# Dial.net
KiCad netlist of a schematic drawn in Altium Designer
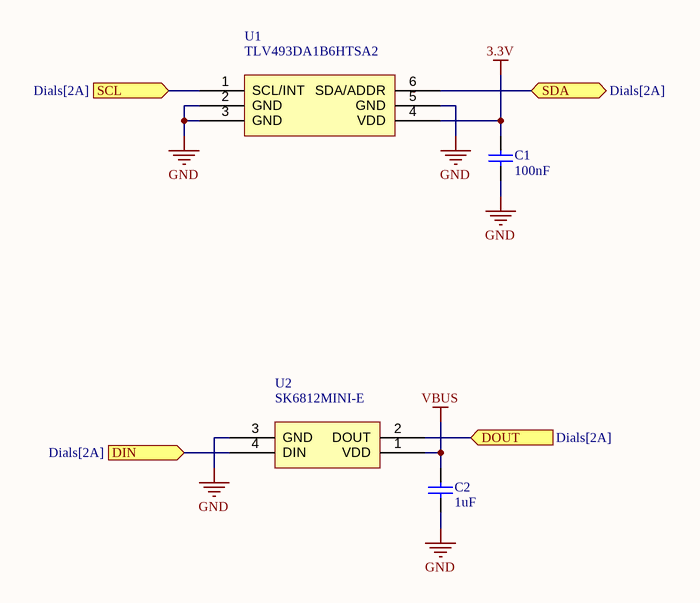
[diagram p0: Dial.SchDoc]

(export (version "E")
  (design (tool "Eeschema 10.0.6"))
  (components
    (comp (ref "C1") (value "100nF") (footprint "Capacitor 0603") (libsource (lib "x-io") (part "Capacitor")))
    (comp (ref "C2") (value "1uF") (footprint "Capacitor 0603") (libsource (lib "x-io") (part "Capacitor")))
    (comp (ref "U1")
      (value "TLV493DA1B6HTSA2")
      (footprint "SOT-23-6")
      (libsource (lib "x-io") (part "TLV493DA1B6HTSA2"))
    )
    (comp (ref "U2")
      (value "SK6812MINI-E")
      (footprint "SK6812MINI-E")
      (libsource (lib "x-io") (part "SK6812MINI-E"))
    )
  )
  (nets
    (net (code "1") (name "/DIN") (class "Default")
      (node (ref "U2") (pin "4") (pinfunction "DIN_4") (pintype "passive"))
    )
    (net (code "2") (name "/DOUT") (class "Default")
      (node (ref "U2") (pin "2") (pinfunction "DOUT_2") (pintype "passive"))
    )
    (net (code "3") (name "/SCL") (class "Default")
      (node (ref "U1") (pin "1") (pinfunction "SCL/INT_1") (pintype "passive"))
    )
    (net (code "4") (name "/SDA") (class "Default")
      (node (ref "U1") (pin "6") (pinfunction "SDA/ADDR_6") (pintype "passive"))
    )
    (net (code "5") (name "3.3V") (class "Default")
      (node (ref "C1") (pin "2") (pinfunction "2_2") (pintype "passive"))
      (node (ref "U1") (pin "4") (pinfunction "VDD_4") (pintype "passive"))
    )
    (net (code "6") (name "GND") (class "Default")
      (node (ref "C1") (pin "1") (pinfunction "1_1") (pintype "passive"))
      (node (ref "C2") (pin "1") (pinfunction "1_1") (pintype "passive"))
      (node (ref "U1") (pin "2") (pinfunction "GND_2") (pintype "passive"))
      (node (ref "U1") (pin "3") (pinfunction "GND_3") (pintype "passive"))
      (node (ref "U1") (pin "5") (pinfunction "GND_5") (pintype "passive"))
      (node (ref "U2") (pin "3") (pinfunction "GND_3") (pintype "passive"))
    )
    (net (code "7") (name "VBUS") (class "Default")
      (node (ref "C2") (pin "2") (pinfunction "2_2") (pintype "passive"))
      (node (ref "U2") (pin "1") (pinfunction "VDD_1") (pintype "passive"))
    )
  )
)
